# 96LED-Board-ALU.net
KiCad netlist of a schematic drawn in EAGLE
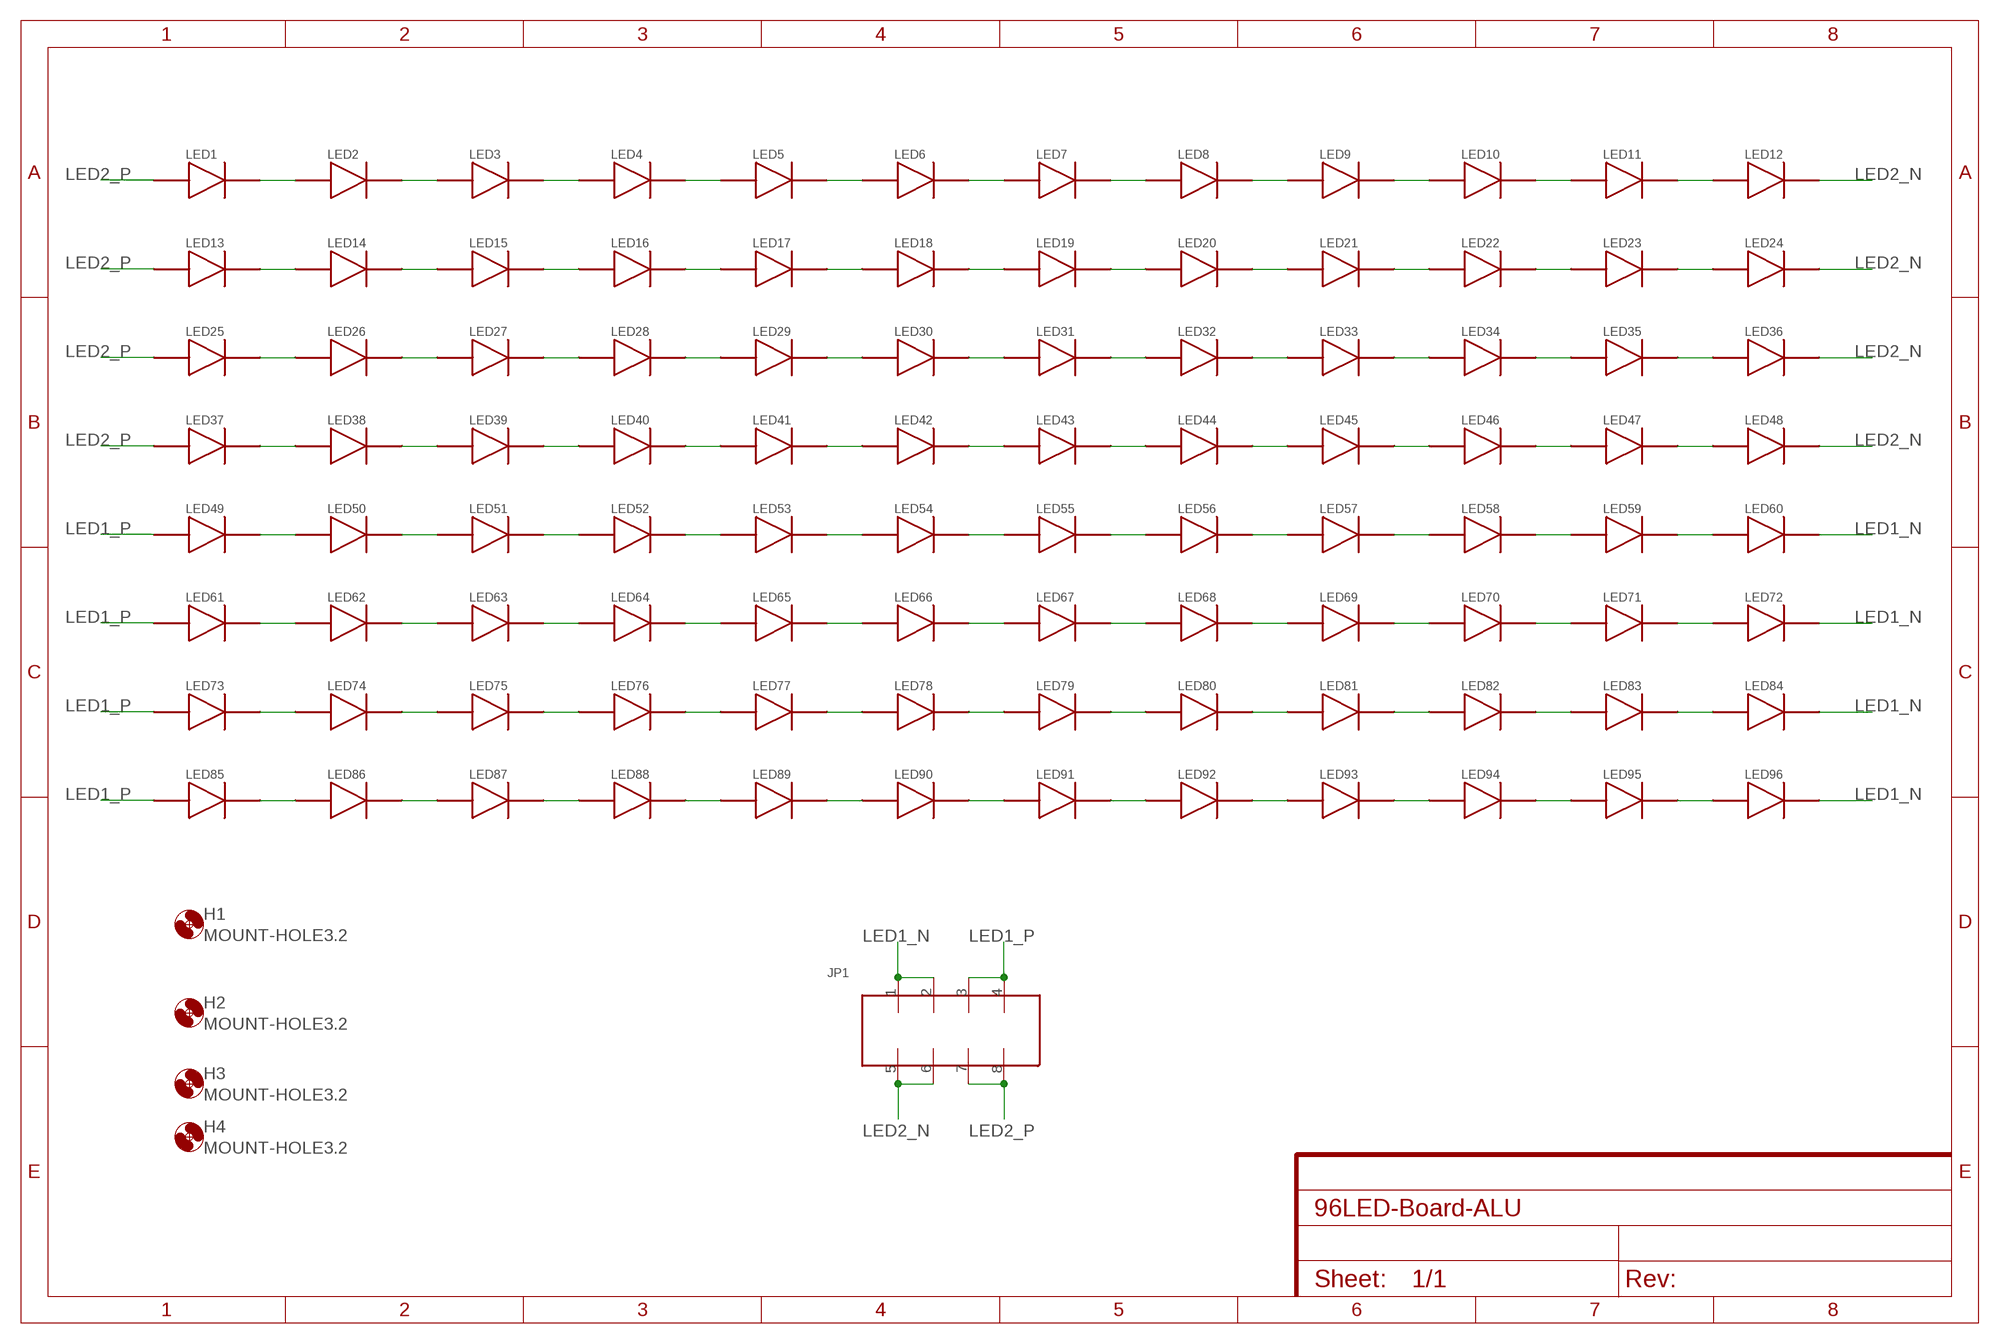
[diagram p0: schematic, sheet 1]

(export (version "E")
  (design (tool "Eeschema 10.0.6"))
  (components
    (comp (ref "H1")
      (value "MOUNT-HOLE3.2")
      (footprint "eagle-import:3,2")
      (libsource (lib "eagle-import") (part "MOUNT-HOLE3.2"))
    )
    (comp (ref "H2")
      (value "MOUNT-HOLE3.2")
      (footprint "eagle-import:3,2")
      (libsource (lib "eagle-import") (part "MOUNT-HOLE3.2"))
    )
    (comp (ref "H3")
      (value "MOUNT-HOLE3.2")
      (footprint "eagle-import:3,2")
      (libsource (lib "eagle-import") (part "MOUNT-HOLE3.2"))
    )
    (comp (ref "H4")
      (value "MOUNT-HOLE3.2")
      (footprint "eagle-import:3,2")
      (libsource (lib "eagle-import") (part "MOUNT-HOLE3.2"))
    )
    (comp (ref "JP1")
      (value "2X8P_2.54_FEMALE")
      (footprint "eagle-import:2X8_PIN_SMD_2.54-FEMALE")
      (libsource (lib "eagle-import") (part "2X8P_2.54_FEMALE"))
    )
    (comp (ref "LED1")
      (value "MP3030_N")
      (footprint "eagle-import:MP3030_N")
      (libsource (lib "eagle-import") (part "MP3030_N"))
    )
    (comp (ref "LED2")
      (value "MP3030_N")
      (footprint "eagle-import:MP3030_N")
      (libsource (lib "eagle-import") (part "MP3030_N"))
    )
    (comp (ref "LED3")
      (value "MP3030_N")
      (footprint "eagle-import:MP3030_N")
      (libsource (lib "eagle-import") (part "MP3030_N"))
    )
    (comp (ref "LED4")
      (value "MP3030_N")
      (footprint "eagle-import:MP3030_N")
      (libsource (lib "eagle-import") (part "MP3030_N"))
    )
    (comp (ref "LED5")
      (value "MP3030_N")
      (footprint "eagle-import:MP3030_N")
      (libsource (lib "eagle-import") (part "MP3030_N"))
    )
    (comp (ref "LED6")
      (value "MP3030_N")
      (footprint "eagle-import:MP3030_N")
      (libsource (lib "eagle-import") (part "MP3030_N"))
    )
    (comp (ref "LED7")
      (value "MP3030_N")
      (footprint "eagle-import:MP3030_N")
      (libsource (lib "eagle-import") (part "MP3030_N"))
    )
    (comp (ref "LED8")
      (value "MP3030_N")
      (footprint "eagle-import:MP3030_N")
      (libsource (lib "eagle-import") (part "MP3030_N"))
    )
    (comp (ref "LED9")
      (value "MP3030_N")
      (footprint "eagle-import:MP3030_N")
      (libsource (lib "eagle-import") (part "MP3030_N"))
    )
    (comp (ref "LED10")
      (value "MP3030_N")
      (footprint "eagle-import:MP3030_N")
      (libsource (lib "eagle-import") (part "MP3030_N"))
    )
    (comp (ref "LED11")
      (value "MP3030_N")
      (footprint "eagle-import:MP3030_N")
      (libsource (lib "eagle-import") (part "MP3030_N"))
    )
    (comp (ref "LED12")
      (value "MP3030_N")
      (footprint "eagle-import:MP3030_N")
      (libsource (lib "eagle-import") (part "MP3030_N"))
    )
    (comp (ref "LED13")
      (value "MP3030_N")
      (footprint "eagle-import:MP3030_N")
      (libsource (lib "eagle-import") (part "MP3030_N"))
    )
    (comp (ref "LED14")
      (value "MP3030_N")
      (footprint "eagle-import:MP3030_N")
      (libsource (lib "eagle-import") (part "MP3030_N"))
    )
    (comp (ref "LED15")
      (value "MP3030_N")
      (footprint "eagle-import:MP3030_N")
      (libsource (lib "eagle-import") (part "MP3030_N"))
    )
    (comp (ref "LED16")
      (value "MP3030_N")
      (footprint "eagle-import:MP3030_N")
      (libsource (lib "eagle-import") (part "MP3030_N"))
    )
    (comp (ref "LED17")
      (value "MP3030_N")
      (footprint "eagle-import:MP3030_N")
      (libsource (lib "eagle-import") (part "MP3030_N"))
    )
    (comp (ref "LED18")
      (value "MP3030_N")
      (footprint "eagle-import:MP3030_N")
      (libsource (lib "eagle-import") (part "MP3030_N"))
    )
    (comp (ref "LED19")
      (value "MP3030_N")
      (footprint "eagle-import:MP3030_N")
      (libsource (lib "eagle-import") (part "MP3030_N"))
    )
    (comp (ref "LED20")
      (value "MP3030_N")
      (footprint "eagle-import:MP3030_N")
      (libsource (lib "eagle-import") (part "MP3030_N"))
    )
    (comp (ref "LED21")
      (value "MP3030_N")
      (footprint "eagle-import:MP3030_N")
      (libsource (lib "eagle-import") (part "MP3030_N"))
    )
    (comp (ref "LED22")
      (value "MP3030_N")
      (footprint "eagle-import:MP3030_N")
      (libsource (lib "eagle-import") (part "MP3030_N"))
    )
    (comp (ref "LED23")
      (value "MP3030_N")
      (footprint "eagle-import:MP3030_N")
      (libsource (lib "eagle-import") (part "MP3030_N"))
    )
    (comp (ref "LED24")
      (value "MP3030_N")
      (footprint "eagle-import:MP3030_N")
      (libsource (lib "eagle-import") (part "MP3030_N"))
    )
    (comp (ref "LED25")
      (value "MP3030_N")
      (footprint "eagle-import:MP3030_N")
      (libsource (lib "eagle-import") (part "MP3030_N"))
    )
    (comp (ref "LED26")
      (value "MP3030_N")
      (footprint "eagle-import:MP3030_N")
      (libsource (lib "eagle-import") (part "MP3030_N"))
    )
    (comp (ref "LED27")
      (value "MP3030_N")
      (footprint "eagle-import:MP3030_N")
      (libsource (lib "eagle-import") (part "MP3030_N"))
    )
    (comp (ref "LED28")
      (value "MP3030_N")
      (footprint "eagle-import:MP3030_N")
      (libsource (lib "eagle-import") (part "MP3030_N"))
    )
    (comp (ref "LED29")
      (value "MP3030_N")
      (footprint "eagle-import:MP3030_N")
      (libsource (lib "eagle-import") (part "MP3030_N"))
    )
    (comp (ref "LED30")
      (value "MP3030_N")
      (footprint "eagle-import:MP3030_N")
      (libsource (lib "eagle-import") (part "MP3030_N"))
    )
    (comp (ref "LED31")
      (value "MP3030_N")
      (footprint "eagle-import:MP3030_N")
      (libsource (lib "eagle-import") (part "MP3030_N"))
    )
    (comp (ref "LED32")
      (value "MP3030_N")
      (footprint "eagle-import:MP3030_N")
      (libsource (lib "eagle-import") (part "MP3030_N"))
    )
    (comp (ref "LED33")
      (value "MP3030_N")
      (footprint "eagle-import:MP3030_N")
      (libsource (lib "eagle-import") (part "MP3030_N"))
    )
    (comp (ref "LED34")
      (value "MP3030_N")
      (footprint "eagle-import:MP3030_N")
      (libsource (lib "eagle-import") (part "MP3030_N"))
    )
    (comp (ref "LED35")
      (value "MP3030_N")
      (footprint "eagle-import:MP3030_N")
      (libsource (lib "eagle-import") (part "MP3030_N"))
    )
    (comp (ref "LED36")
      (value "MP3030_N")
      (footprint "eagle-import:MP3030_N")
      (libsource (lib "eagle-import") (part "MP3030_N"))
    )
    (comp (ref "LED37")
      (value "MP3030_N")
      (footprint "eagle-import:MP3030_N")
      (libsource (lib "eagle-import") (part "MP3030_N"))
    )
    (comp (ref "LED38")
      (value "MP3030_N")
      (footprint "eagle-import:MP3030_N")
      (libsource (lib "eagle-import") (part "MP3030_N"))
    )
    (comp (ref "LED39")
      (value "MP3030_N")
      (footprint "eagle-import:MP3030_N")
      (libsource (lib "eagle-import") (part "MP3030_N"))
    )
    (comp (ref "LED40")
      (value "MP3030_N")
      (footprint "eagle-import:MP3030_N")
      (libsource (lib "eagle-import") (part "MP3030_N"))
    )
    (comp (ref "LED41")
      (value "MP3030_N")
      (footprint "eagle-import:MP3030_N")
      (libsource (lib "eagle-import") (part "MP3030_N"))
    )
    (comp (ref "LED42")
      (value "MP3030_N")
      (footprint "eagle-import:MP3030_N")
      (libsource (lib "eagle-import") (part "MP3030_N"))
    )
    (comp (ref "LED43")
      (value "MP3030_N")
      (footprint "eagle-import:MP3030_N")
      (libsource (lib "eagle-import") (part "MP3030_N"))
    )
    (comp (ref "LED44")
      (value "MP3030_N")
      (footprint "eagle-import:MP3030_N")
      (libsource (lib "eagle-import") (part "MP3030_N"))
    )
    (comp (ref "LED45")
      (value "MP3030_N")
      (footprint "eagle-import:MP3030_N")
      (libsource (lib "eagle-import") (part "MP3030_N"))
    )
    (comp (ref "LED46")
      (value "MP3030_N")
      (footprint "eagle-import:MP3030_N")
      (libsource (lib "eagle-import") (part "MP3030_N"))
    )
    (comp (ref "LED47")
      (value "MP3030_N")
      (footprint "eagle-import:MP3030_N")
      (libsource (lib "eagle-import") (part "MP3030_N"))
    )
    (comp (ref "LED48")
      (value "MP3030_N")
      (footprint "eagle-import:MP3030_N")
      (libsource (lib "eagle-import") (part "MP3030_N"))
    )
    (comp (ref "LED49")
      (value "MP3030_N")
      (footprint "eagle-import:MP3030_N")
      (libsource (lib "eagle-import") (part "MP3030_N"))
    )
    (comp (ref "LED50")
      (value "MP3030_N")
      (footprint "eagle-import:MP3030_N")
      (libsource (lib "eagle-import") (part "MP3030_N"))
    )
    (comp (ref "LED51")
      (value "MP3030_N")
      (footprint "eagle-import:MP3030_N")
      (libsource (lib "eagle-import") (part "MP3030_N"))
    )
    (comp (ref "LED52")
      (value "MP3030_N")
      (footprint "eagle-import:MP3030_N")
      (libsource (lib "eagle-import") (part "MP3030_N"))
    )
    (comp (ref "LED53")
      (value "MP3030_N")
      (footprint "eagle-import:MP3030_N")
      (libsource (lib "eagle-import") (part "MP3030_N"))
    )
    (comp (ref "LED54")
      (value "MP3030_N")
      (footprint "eagle-import:MP3030_N")
      (libsource (lib "eagle-import") (part "MP3030_N"))
    )
    (comp (ref "LED55")
      (value "MP3030_N")
      (footprint "eagle-import:MP3030_N")
      (libsource (lib "eagle-import") (part "MP3030_N"))
    )
    (comp (ref "LED56")
      (value "MP3030_N")
      (footprint "eagle-import:MP3030_N")
      (libsource (lib "eagle-import") (part "MP3030_N"))
    )
    (comp (ref "LED57")
      (value "MP3030_N")
      (footprint "eagle-import:MP3030_N")
      (libsource (lib "eagle-import") (part "MP3030_N"))
    )
    (comp (ref "LED58")
      (value "MP3030_N")
      (footprint "eagle-import:MP3030_N")
      (libsource (lib "eagle-import") (part "MP3030_N"))
    )
    (comp (ref "LED59")
      (value "MP3030_N")
      (footprint "eagle-import:MP3030_N")
      (libsource (lib "eagle-import") (part "MP3030_N"))
    )
    (comp (ref "LED60")
      (value "MP3030_N")
      (footprint "eagle-import:MP3030_N")
      (libsource (lib "eagle-import") (part "MP3030_N"))
    )
    (comp (ref "LED61")
      (value "MP3030_N")
      (footprint "eagle-import:MP3030_N")
      (libsource (lib "eagle-import") (part "MP3030_N"))
    )
    (comp (ref "LED62")
      (value "MP3030_N")
      (footprint "eagle-import:MP3030_N")
      (libsource (lib "eagle-import") (part "MP3030_N"))
    )
    (comp (ref "LED63")
      (value "MP3030_N")
      (footprint "eagle-import:MP3030_N")
      (libsource (lib "eagle-import") (part "MP3030_N"))
    )
    (comp (ref "LED64")
      (value "MP3030_N")
      (footprint "eagle-import:MP3030_N")
      (libsource (lib "eagle-import") (part "MP3030_N"))
    )
    (comp (ref "LED65")
      (value "MP3030_N")
      (footprint "eagle-import:MP3030_N")
      (libsource (lib "eagle-import") (part "MP3030_N"))
    )
    (comp (ref "LED66")
      (value "MP3030_N")
      (footprint "eagle-import:MP3030_N")
      (libsource (lib "eagle-import") (part "MP3030_N"))
    )
    (comp (ref "LED67")
      (value "MP3030_N")
      (footprint "eagle-import:MP3030_N")
      (libsource (lib "eagle-import") (part "MP3030_N"))
    )
    (comp (ref "LED68")
      (value "MP3030_N")
      (footprint "eagle-import:MP3030_N")
      (libsource (lib "eagle-import") (part "MP3030_N"))
    )
    (comp (ref "LED69")
      (value "MP3030_N")
      (footprint "eagle-import:MP3030_N")
      (libsource (lib "eagle-import") (part "MP3030_N"))
    )
    (comp (ref "LED70")
      (value "MP3030_N")
      (footprint "eagle-import:MP3030_N")
      (libsource (lib "eagle-import") (part "MP3030_N"))
    )
    (comp (ref "LED71")
      (value "MP3030_N")
      (footprint "eagle-import:MP3030_N")
      (libsource (lib "eagle-import") (part "MP3030_N"))
    )
    (comp (ref "LED72")
      (value "MP3030_N")
      (footprint "eagle-import:MP3030_N")
      (libsource (lib "eagle-import") (part "MP3030_N"))
    )
    (comp (ref "LED73")
      (value "MP3030_N")
      (footprint "eagle-import:MP3030_N")
      (libsource (lib "eagle-import") (part "MP3030_N"))
    )
    (comp (ref "LED74")
      (value "MP3030_N")
      (footprint "eagle-import:MP3030_N")
      (libsource (lib "eagle-import") (part "MP3030_N"))
    )
    (comp (ref "LED75")
      (value "MP3030_N")
      (footprint "eagle-import:MP3030_N")
      (libsource (lib "eagle-import") (part "MP3030_N"))
    )
    (comp (ref "LED76")
      (value "MP3030_N")
      (footprint "eagle-import:MP3030_N")
      (libsource (lib "eagle-import") (part "MP3030_N"))
    )
    (comp (ref "LED77")
      (value "MP3030_N")
      (footprint "eagle-import:MP3030_N")
      (libsource (lib "eagle-import") (part "MP3030_N"))
    )
    (comp (ref "LED78")
      (value "MP3030_N")
      (footprint "eagle-import:MP3030_N")
      (libsource (lib "eagle-import") (part "MP3030_N"))
    )
    (comp (ref "LED79")
      (value "MP3030_N")
      (footprint "eagle-import:MP3030_N")
      (libsource (lib "eagle-import") (part "MP3030_N"))
    )
    (comp (ref "LED80")
      (value "MP3030_N")
      (footprint "eagle-import:MP3030_N")
      (libsource (lib "eagle-import") (part "MP3030_N"))
    )
    (comp (ref "LED81")
      (value "MP3030_N")
      (footprint "eagle-import:MP3030_N")
      (libsource (lib "eagle-import") (part "MP3030_N"))
    )
    (comp (ref "LED82")
      (value "MP3030_N")
      (footprint "eagle-import:MP3030_N")
      (libsource (lib "eagle-import") (part "MP3030_N"))
    )
    (comp (ref "LED83")
      (value "MP3030_N")
      (footprint "eagle-import:MP3030_N")
      (libsource (lib "eagle-import") (part "MP3030_N"))
    )
    (comp (ref "LED84")
      (value "MP3030_N")
      (footprint "eagle-import:MP3030_N")
      (libsource (lib "eagle-import") (part "MP3030_N"))
    )
    (comp (ref "LED85")
      (value "MP3030_N")
      (footprint "eagle-import:MP3030_N")
      (libsource (lib "eagle-import") (part "MP3030_N"))
    )
    (comp (ref "LED86")
      (value "MP3030_N")
      (footprint "eagle-import:MP3030_N")
      (libsource (lib "eagle-import") (part "MP3030_N"))
    )
    (comp (ref "LED87")
      (value "MP3030_N")
      (footprint "eagle-import:MP3030_N")
      (libsource (lib "eagle-import") (part "MP3030_N"))
    )
    (comp (ref "LED88")
      (value "MP3030_N")
      (footprint "eagle-import:MP3030_N")
      (libsource (lib "eagle-import") (part "MP3030_N"))
    )
    (comp (ref "LED89")
      (value "MP3030_N")
      (footprint "eagle-import:MP3030_N")
      (libsource (lib "eagle-import") (part "MP3030_N"))
    )
    (comp (ref "LED90")
      (value "MP3030_N")
      (footprint "eagle-import:MP3030_N")
      (libsource (lib "eagle-import") (part "MP3030_N"))
    )
    (comp (ref "LED91")
      (value "MP3030_N")
      (footprint "eagle-import:MP3030_N")
      (libsource (lib "eagle-import") (part "MP3030_N"))
    )
    (comp (ref "LED92")
      (value "MP3030_N")
      (footprint "eagle-import:MP3030_N")
      (libsource (lib "eagle-import") (part "MP3030_N"))
    )
    (comp (ref "LED93")
      (value "MP3030_N")
      (footprint "eagle-import:MP3030_N")
      (libsource (lib "eagle-import") (part "MP3030_N"))
    )
    (comp (ref "LED94")
      (value "MP3030_N")
      (footprint "eagle-import:MP3030_N")
      (libsource (lib "eagle-import") (part "MP3030_N"))
    )
    (comp (ref "LED95")
      (value "MP3030_N")
      (footprint "eagle-import:MP3030_N")
      (libsource (lib "eagle-import") (part "MP3030_N"))
    )
    (comp (ref "LED96")
      (value "MP3030_N")
      (footprint "eagle-import:MP3030_N")
      (libsource (lib "eagle-import") (part "MP3030_N"))
    )
  )
  (nets
    (net (code "1") (name "/LED1_N") (class "Default")
      (node (ref "JP1") (pin "1") (pinfunction "P$1_1") (pintype "bidirectional"))
      (node (ref "JP1") (pin "2") (pinfunction "P$2_2") (pintype "bidirectional"))
      (node (ref "LED60") (pin "2") (pinfunction "2_2") (pintype "bidirectional"))
      (node (ref "LED72") (pin "2") (pinfunction "2_2") (pintype "bidirectional"))
      (node (ref "LED84") (pin "2") (pinfunction "2_2") (pintype "bidirectional"))
      (node (ref "LED96") (pin "2") (pinfunction "2_2") (pintype "bidirectional"))
    )
    (net (code "2") (name "/LED1_P") (class "Default")
      (node (ref "JP1") (pin "3") (pinfunction "P$3_3") (pintype "bidirectional"))
      (node (ref "JP1") (pin "4") (pinfunction "P$4_4") (pintype "bidirectional"))
      (node (ref "LED49") (pin "1") (pinfunction "1_1") (pintype "bidirectional"))
      (node (ref "LED61") (pin "1") (pinfunction "1_1") (pintype "bidirectional"))
      (node (ref "LED73") (pin "1") (pinfunction "1_1") (pintype "bidirectional"))
      (node (ref "LED85") (pin "1") (pinfunction "1_1") (pintype "bidirectional"))
    )
    (net (code "3") (name "/LED2_N") (class "Default")
      (node (ref "JP1") (pin "5") (pinfunction "P$5_5") (pintype "bidirectional"))
      (node (ref "JP1") (pin "6") (pinfunction "P$6_6") (pintype "bidirectional"))
      (node (ref "LED12") (pin "2") (pinfunction "2_2") (pintype "bidirectional"))
      (node (ref "LED24") (pin "2") (pinfunction "2_2") (pintype "bidirectional"))
      (node (ref "LED36") (pin "2") (pinfunction "2_2") (pintype "bidirectional"))
      (node (ref "LED48") (pin "2") (pinfunction "2_2") (pintype "bidirectional"))
    )
    (net (code "4") (name "/LED2_P") (class "Default")
      (node (ref "JP1") (pin "7") (pinfunction "P$7_7") (pintype "bidirectional"))
      (node (ref "JP1") (pin "8") (pinfunction "P$8_8") (pintype "bidirectional"))
      (node (ref "LED1") (pin "1") (pinfunction "1_1") (pintype "bidirectional"))
      (node (ref "LED13") (pin "1") (pinfunction "1_1") (pintype "bidirectional"))
      (node (ref "LED25") (pin "1") (pinfunction "1_1") (pintype "bidirectional"))
      (node (ref "LED37") (pin "1") (pinfunction "1_1") (pintype "bidirectional"))
    )
    (net (code "5") (name "Net-(LED1-Pad2)") (class "Default")
      (node (ref "LED1") (pin "2") (pinfunction "2_2") (pintype "bidirectional"))
      (node (ref "LED2") (pin "1") (pinfunction "1_1") (pintype "bidirectional"))
    )
    (net (code "6") (name "Net-(LED2-Pad2)") (class "Default")
      (node (ref "LED2") (pin "2") (pinfunction "2_2") (pintype "bidirectional"))
      (node (ref "LED3") (pin "1") (pinfunction "1_1") (pintype "bidirectional"))
    )
    (net (code "7") (name "Net-(LED3-Pad2)") (class "Default")
      (node (ref "LED3") (pin "2") (pinfunction "2_2") (pintype "bidirectional"))
      (node (ref "LED4") (pin "1") (pinfunction "1_1") (pintype "bidirectional"))
    )
    (net (code "8") (name "Net-(LED4-Pad2)") (class "Default")
      (node (ref "LED4") (pin "2") (pinfunction "2_2") (pintype "bidirectional"))
      (node (ref "LED5") (pin "1") (pinfunction "1_1") (pintype "bidirectional"))
    )
    (net (code "9") (name "Net-(LED5-Pad2)") (class "Default")
      (node (ref "LED5") (pin "2") (pinfunction "2_2") (pintype "bidirectional"))
      (node (ref "LED6") (pin "1") (pinfunction "1_1") (pintype "bidirectional"))
    )
    (net (code "10") (name "Net-(LED6-Pad2)") (class "Default")
      (node (ref "LED6") (pin "2") (pinfunction "2_2") (pintype "bidirectional"))
      (node (ref "LED7") (pin "1") (pinfunction "1_1") (pintype "bidirectional"))
    )
    (net (code "11") (name "Net-(LED7-Pad2)") (class "Default")
      (node (ref "LED7") (pin "2") (pinfunction "2_2") (pintype "bidirectional"))
      (node (ref "LED8") (pin "1") (pinfunction "1_1") (pintype "bidirectional"))
    )
    (net (code "12") (name "Net-(LED8-Pad2)") (class "Default")
      (node (ref "LED8") (pin "2") (pinfunction "2_2") (pintype "bidirectional"))
      (node (ref "LED9") (pin "1") (pinfunction "1_1") (pintype "bidirectional"))
    )
    (net (code "13") (name "Net-(LED10-Pad1)") (class "Default")
      (node (ref "LED10") (pin "1") (pinfunction "1_1") (pintype "bidirectional"))
      (node (ref "LED9") (pin "2") (pinfunction "2_2") (pintype "bidirectional"))
    )
    (net (code "14") (name "Net-(LED10-Pad2)") (class "Default")
      (node (ref "LED10") (pin "2") (pinfunction "2_2") (pintype "bidirectional"))
      (node (ref "LED11") (pin "1") (pinfunction "1_1") (pintype "bidirectional"))
    )
    (net (code "15") (name "Net-(LED11-Pad2)") (class "Default")
      (node (ref "LED11") (pin "2") (pinfunction "2_2") (pintype "bidirectional"))
      (node (ref "LED12") (pin "1") (pinfunction "1_1") (pintype "bidirectional"))
    )
    (net (code "16") (name "Net-(LED13-Pad2)") (class "Default")
      (node (ref "LED13") (pin "2") (pinfunction "2_2") (pintype "bidirectional"))
      (node (ref "LED14") (pin "1") (pinfunction "1_1") (pintype "bidirectional"))
    )
    (net (code "17") (name "Net-(LED14-Pad2)") (class "Default")
      (node (ref "LED14") (pin "2") (pinfunction "2_2") (pintype "bidirectional"))
      (node (ref "LED15") (pin "1") (pinfunction "1_1") (pintype "bidirectional"))
    )
    (net (code "18") (name "Net-(LED15-Pad2)") (class "Default")
      (node (ref "LED15") (pin "2") (pinfunction "2_2") (pintype "bidirectional"))
      (node (ref "LED16") (pin "1") (pinfunction "1_1") (pintype "bidirectional"))
    )
    (net (code "19") (name "Net-(LED16-Pad2)") (class "Default")
      (node (ref "LED16") (pin "2") (pinfunction "2_2") (pintype "bidirectional"))
      (node (ref "LED17") (pin "1") (pinfunction "1_1") (pintype "bidirectional"))
    )
    (net (code "20") (name "Net-(LED17-Pad2)") (class "Default")
      (node (ref "LED17") (pin "2") (pinfunction "2_2") (pintype "bidirectional"))
      (node (ref "LED18") (pin "1") (pinfunction "1_1") (pintype "bidirectional"))
    )
    (net (code "21") (name "Net-(LED18-Pad2)") (class "Default")
      (node (ref "LED18") (pin "2") (pinfunction "2_2") (pintype "bidirectional"))
      (node (ref "LED19") (pin "1") (pinfunction "1_1") (pintype "bidirectional"))
    )
    (net (code "22") (name "Net-(LED19-Pad2)") (class "Default")
      (node (ref "LED19") (pin "2") (pinfunction "2_2") (pintype "bidirectional"))
      (node (ref "LED20") (pin "1") (pinfunction "1_1") (pintype "bidirectional"))
    )
    (net (code "23") (name "Net-(LED20-Pad2)") (class "Default")
      (node (ref "LED20") (pin "2") (pinfunction "2_2") (pintype "bidirectional"))
      (node (ref "LED21") (pin "1") (pinfunction "1_1") (pintype "bidirectional"))
    )
    (net (code "24") (name "Net-(LED21-Pad2)") (class "Default")
      (node (ref "LED21") (pin "2") (pinfunction "2_2") (pintype "bidirectional"))
      (node (ref "LED22") (pin "1") (pinfunction "1_1") (pintype "bidirectional"))
    )
    (net (code "25") (name "Net-(LED22-Pad2)") (class "Default")
      (node (ref "LED22") (pin "2") (pinfunction "2_2") (pintype "bidirectional"))
      (node (ref "LED23") (pin "1") (pinfunction "1_1") (pintype "bidirectional"))
    )
    (net (code "26") (name "Net-(LED23-Pad2)") (class "Default")
      (node (ref "LED23") (pin "2") (pinfunction "2_2") (pintype "bidirectional"))
      (node (ref "LED24") (pin "1") (pinfunction "1_1") (pintype "bidirectional"))
    )
    (net (code "27") (name "Net-(LED25-Pad2)") (class "Default")
      (node (ref "LED25") (pin "2") (pinfunction "2_2") (pintype "bidirectional"))
      (node (ref "LED26") (pin "1") (pinfunction "1_1") (pintype "bidirectional"))
    )
    (net (code "28") (name "Net-(LED26-Pad2)") (class "Default")
      (node (ref "LED26") (pin "2") (pinfunction "2_2") (pintype "bidirectional"))
      (node (ref "LED27") (pin "1") (pinfunction "1_1") (pintype "bidirectional"))
    )
    (net (code "29") (name "Net-(LED27-Pad2)") (class "Default")
      (node (ref "LED27") (pin "2") (pinfunction "2_2") (pintype "bidirectional"))
      (node (ref "LED28") (pin "1") (pinfunction "1_1") (pintype "bidirectional"))
    )
    (net (code "30") (name "Net-(LED28-Pad2)") (class "Default")
      (node (ref "LED28") (pin "2") (pinfunction "2_2") (pintype "bidirectional"))
      (node (ref "LED29") (pin "1") (pinfunction "1_1") (pintype "bidirectional"))
    )
    (net (code "31") (name "Net-(LED29-Pad2)") (class "Default")
      (node (ref "LED29") (pin "2") (pinfunction "2_2") (pintype "bidirectional"))
      (node (ref "LED30") (pin "1") (pinfunction "1_1") (pintype "bidirectional"))
    )
    (net (code "32") (name "Net-(LED30-Pad2)") (class "Default")
      (node (ref "LED30") (pin "2") (pinfunction "2_2") (pintype "bidirectional"))
      (node (ref "LED31") (pin "1") (pinfunction "1_1") (pintype "bidirectional"))
    )
    (net (code "33") (name "Net-(LED31-Pad2)") (class "Default")
      (node (ref "LED31") (pin "2") (pinfunction "2_2") (pintype "bidirectional"))
      (node (ref "LED32") (pin "1") (pinfunction "1_1") (pintype "bidirectional"))
    )
    (net (code "34") (name "Net-(LED32-Pad2)") (class "Default")
      (node (ref "LED32") (pin "2") (pinfunction "2_2") (pintype "bidirectional"))
      (node (ref "LED33") (pin "1") (pinfunction "1_1") (pintype "bidirectional"))
    )
    (net (code "35") (name "Net-(LED33-Pad2)") (class "Default")
      (node (ref "LED33") (pin "2") (pinfunction "2_2") (pintype "bidirectional"))
      (node (ref "LED34") (pin "1") (pinfunction "1_1") (pintype "bidirectional"))
    )
    (net (code "36") (name "Net-(LED34-Pad2)") (class "Default")
      (node (ref "LED34") (pin "2") (pinfunction "2_2") (pintype "bidirectional"))
      (node (ref "LED35") (pin "1") (pinfunction "1_1") (pintype "bidirectional"))
    )
    (net (code "37") (name "Net-(LED35-Pad2)") (class "Default")
      (node (ref "LED35") (pin "2") (pinfunction "2_2") (pintype "bidirectional"))
      (node (ref "LED36") (pin "1") (pinfunction "1_1") (pintype "bidirectional"))
    )
    (net (code "38") (name "Net-(LED37-Pad2)") (class "Default")
      (node (ref "LED37") (pin "2") (pinfunction "2_2") (pintype "bidirectional"))
      (node (ref "LED38") (pin "1") (pinfunction "1_1") (pintype "bidirectional"))
    )
    (net (code "39") (name "Net-(LED38-Pad2)") (class "Default")
      (node (ref "LED38") (pin "2") (pinfunction "2_2") (pintype "bidirectional"))
      (node (ref "LED39") (pin "1") (pinfunction "1_1") (pintype "bidirectional"))
    )
    (net (code "40") (name "Net-(LED39-Pad2)") (class "Default")
      (node (ref "LED39") (pin "2") (pinfunction "2_2") (pintype "bidirectional"))
      (node (ref "LED40") (pin "1") (pinfunction "1_1") (pintype "bidirectional"))
    )
    (net (code "41") (name "Net-(LED40-Pad2)") (class "Default")
      (node (ref "LED40") (pin "2") (pinfunction "2_2") (pintype "bidirectional"))
      (node (ref "LED41") (pin "1") (pinfunction "1_1") (pintype "bidirectional"))
    )
    (net (code "42") (name "Net-(LED41-Pad2)") (class "Default")
      (node (ref "LED41") (pin "2") (pinfunction "2_2") (pintype "bidirectional"))
      (node (ref "LED42") (pin "1") (pinfunction "1_1") (pintype "bidirectional"))
    )
    (net (code "43") (name "Net-(LED42-Pad2)") (class "Default")
      (node (ref "LED42") (pin "2") (pinfunction "2_2") (pintype "bidirectional"))
      (node (ref "LED43") (pin "1") (pinfunction "1_1") (pintype "bidirectional"))
    )
    (net (code "44") (name "Net-(LED43-Pad2)") (class "Default")
      (node (ref "LED43") (pin "2") (pinfunction "2_2") (pintype "bidirectional"))
      (node (ref "LED44") (pin "1") (pinfunction "1_1") (pintype "bidirectional"))
    )
    (net (code "45") (name "Net-(LED44-Pad2)") (class "Default")
      (node (ref "LED44") (pin "2") (pinfunction "2_2") (pintype "bidirectional"))
      (node (ref "LED45") (pin "1") (pinfunction "1_1") (pintype "bidirectional"))
    )
    (net (code "46") (name "Net-(LED45-Pad2)") (class "Default")
      (node (ref "LED45") (pin "2") (pinfunction "2_2") (pintype "bidirectional"))
      (node (ref "LED46") (pin "1") (pinfunction "1_1") (pintype "bidirectional"))
    )
    (net (code "47") (name "Net-(LED46-Pad2)") (class "Default")
      (node (ref "LED46") (pin "2") (pinfunction "2_2") (pintype "bidirectional"))
      (node (ref "LED47") (pin "1") (pinfunction "1_1") (pintype "bidirectional"))
    )
    (net (code "48") (name "Net-(LED47-Pad2)") (class "Default")
      (node (ref "LED47") (pin "2") (pinfunction "2_2") (pintype "bidirectional"))
      (node (ref "LED48") (pin "1") (pinfunction "1_1") (pintype "bidirectional"))
    )
    (net (code "49") (name "Net-(LED49-Pad2)") (class "Default")
      (node (ref "LED49") (pin "2") (pinfunction "2_2") (pintype "bidirectional"))
      (node (ref "LED50") (pin "1") (pinfunction "1_1") (pintype "bidirectional"))
    )
    (net (code "50") (name "Net-(LED50-Pad2)") (class "Default")
      (node (ref "LED50") (pin "2") (pinfunction "2_2") (pintype "bidirectional"))
      (node (ref "LED51") (pin "1") (pinfunction "1_1") (pintype "bidirectional"))
    )
    (net (code "51") (name "Net-(LED51-Pad2)") (class "Default")
      (node (ref "LED51") (pin "2") (pinfunction "2_2") (pintype "bidirectional"))
      (node (ref "LED52") (pin "1") (pinfunction "1_1") (pintype "bidirectional"))
    )
    (net (code "52") (name "Net-(LED52-Pad2)") (class "Default")
      (node (ref "LED52") (pin "2") (pinfunction "2_2") (pintype "bidirectional"))
      (node (ref "LED53") (pin "1") (pinfunction "1_1") (pintype "bidirectional"))
    )
    (net (code "53") (name "Net-(LED53-Pad2)") (class "Default")
      (node (ref "LED53") (pin "2") (pinfunction "2_2") (pintype "bidirectional"))
      (node (ref "LED54") (pin "1") (pinfunction "1_1") (pintype "bidirectional"))
    )
    (net (code "54") (name "Net-(LED54-Pad2)") (class "Default")
      (node (ref "LED54") (pin "2") (pinfunction "2_2") (pintype "bidirectional"))
      (node (ref "LED55") (pin "1") (pinfunction "1_1") (pintype "bidirectional"))
    )
    (net (code "55") (name "Net-(LED55-Pad2)") (class "Default")
      (node (ref "LED55") (pin "2") (pinfunction "2_2") (pintype "bidirectional"))
      (node (ref "LED56") (pin "1") (pinfunction "1_1") (pintype "bidirectional"))
    )
    (net (code "56") (name "Net-(LED56-Pad2)") (class "Default")
      (node (ref "LED56") (pin "2") (pinfunction "2_2") (pintype "bidirectional"))
      (node (ref "LED57") (pin "1") (pinfunction "1_1") (pintype "bidirectional"))
    )
    (net (code "57") (name "Net-(LED57-Pad2)") (class "Default")
      (node (ref "LED57") (pin "2") (pinfunction "2_2") (pintype "bidirectional"))
      (node (ref "LED58") (pin "1") (pinfunction "1_1") (pintype "bidirectional"))
    )
    (net (code "58") (name "Net-(LED58-Pad2)") (class "Default")
      (node (ref "LED58") (pin "2") (pinfunction "2_2") (pintype "bidirectional"))
      (node (ref "LED59") (pin "1") (pinfunction "1_1") (pintype "bidirectional"))
    )
    (net (code "59") (name "Net-(LED59-Pad2)") (class "Default")
      (node (ref "LED59") (pin "2") (pinfunction "2_2") (pintype "bidirectional"))
      (node (ref "LED60") (pin "1") (pinfunction "1_1") (pintype "bidirectional"))
    )
    (net (code "60") (name "Net-(LED61-Pad2)") (class "Default")
      (node (ref "LED61") (pin "2") (pinfunction "2_2") (pintype "bidirectional"))
      (node (ref "LED62") (pin "1") (pinfunction "1_1") (pintype "bidirectional"))
    )
    (net (code "61") (name "Net-(LED62-Pad2)") (class "Default")
      (node (ref "LED62") (pin "2") (pinfunction "2_2") (pintype "bidirectional"))
      (node (ref "LED63") (pin "1") (pinfunction "1_1") (pintype "bidirectional"))
    )
    (net (code "62") (name "Net-(LED63-Pad2)") (class "Default")
      (node (ref "LED63") (pin "2") (pinfunction "2_2") (pintype "bidirectional"))
      (node (ref "LED64") (pin "1") (pinfunction "1_1") (pintype "bidirectional"))
    )
    (net (code "63") (name "Net-(LED64-Pad2)") (class "Default")
      (node (ref "LED64") (pin "2") (pinfunction "2_2") (pintype "bidirectional"))
      (node (ref "LED65") (pin "1") (pinfunction "1_1") (pintype "bidirectional"))
    )
    (net (code "64") (name "Net-(LED65-Pad2)") (class "Default")
      (node (ref "LED65") (pin "2") (pinfunction "2_2") (pintype "bidirectional"))
      (node (ref "LED66") (pin "1") (pinfunction "1_1") (pintype "bidirectional"))
    )
    (net (code "65") (name "Net-(LED66-Pad2)") (class "Default")
      (node (ref "LED66") (pin "2") (pinfunction "2_2") (pintype "bidirectional"))
      (node (ref "LED67") (pin "1") (pinfunction "1_1") (pintype "bidirectional"))
    )
    (net (code "66") (name "Net-(LED67-Pad2)") (class "Default")
      (node (ref "LED67") (pin "2") (pinfunction "2_2") (pintype "bidirectional"))
      (node (ref "LED68") (pin "1") (pinfunction "1_1") (pintype "bidirectional"))
    )
    (net (code "67") (name "Net-(LED68-Pad2)") (class "Default")
      (node (ref "LED68") (pin "2") (pinfunction "2_2") (pintype "bidirectional"))
      (node (ref "LED69") (pin "1") (pinfunction "1_1") (pintype "bidirectional"))
    )
    (net (code "68") (name "Net-(LED69-Pad2)") (class "Default")
      (node (ref "LED69") (pin "2") (pinfunction "2_2") (pintype "bidirectional"))
      (node (ref "LED70") (pin "1") (pinfunction "1_1") (pintype "bidirectional"))
    )
    (net (code "69") (name "Net-(LED70-Pad2)") (class "Default")
      (node (ref "LED70") (pin "2") (pinfunction "2_2") (pintype "bidirectional"))
      (node (ref "LED71") (pin "1") (pinfunction "1_1") (pintype "bidirectional"))
    )
    (net (code "70") (name "Net-(LED71-Pad2)") (class "Default")
      (node (ref "LED71") (pin "2") (pinfunction "2_2") (pintype "bidirectional"))
      (node (ref "LED72") (pin "1") (pinfunction "1_1") (pintype "bidirectional"))
    )
    (net (code "71") (name "Net-(LED73-Pad2)") (class "Default")
      (node (ref "LED73") (pin "2") (pinfunction "2_2") (pintype "bidirectional"))
      (node (ref "LED74") (pin "1") (pinfunction "1_1") (pintype "bidirectional"))
    )
    (net (code "72") (name "Net-(LED74-Pad2)") (class "Default")
      (node (ref "LED74") (pin "2") (pinfunction "2_2") (pintype "bidirectional"))
      (node (ref "LED75") (pin "1") (pinfunction "1_1") (pintype "bidirectional"))
    )
    (net (code "73") (name "Net-(LED75-Pad2)") (class "Default")
      (node (ref "LED75") (pin "2") (pinfunction "2_2") (pintype "bidirectional"))
      (node (ref "LED76") (pin "1") (pinfunction "1_1") (pintype "bidirectional"))
    )
    (net (code "74") (name "Net-(LED76-Pad2)") (class "Default")
      (node (ref "LED76") (pin "2") (pinfunction "2_2") (pintype "bidirectional"))
      (node (ref "LED77") (pin "1") (pinfunction "1_1") (pintype "bidirectional"))
    )
    (net (code "75") (name "Net-(LED77-Pad2)") (class "Default")
      (node (ref "LED77") (pin "2") (pinfunction "2_2") (pintype "bidirectional"))
      (node (ref "LED78") (pin "1") (pinfunction "1_1") (pintype "bidirectional"))
    )
    (net (code "76") (name "Net-(LED78-Pad2)") (class "Default")
      (node (ref "LED78") (pin "2") (pinfunction "2_2") (pintype "bidirectional"))
      (node (ref "LED79") (pin "1") (pinfunction "1_1") (pintype "bidirectional"))
    )
    (net (code "77") (name "Net-(LED79-Pad2)") (class "Default")
      (node (ref "LED79") (pin "2") (pinfunction "2_2") (pintype "bidirectional"))
      (node (ref "LED80") (pin "1") (pinfunction "1_1") (pintype "bidirectional"))
    )
    (net (code "78") (name "Net-(LED80-Pad2)") (class "Default")
      (node (ref "LED80") (pin "2") (pinfunction "2_2") (pintype "bidirectional"))
      (node (ref "LED81") (pin "1") (pinfunction "1_1") (pintype "bidirectional"))
    )
    (net (code "79") (name "Net-(LED81-Pad2)") (class "Default")
      (node (ref "LED81") (pin "2") (pinfunction "2_2") (pintype "bidirectional"))
      (node (ref "LED82") (pin "1") (pinfunction "1_1") (pintype "bidirectional"))
    )
    (net (code "80") (name "Net-(LED82-Pad2)") (class "Default")
      (node (ref "LED82") (pin "2") (pinfunction "2_2") (pintype "bidirectional"))
      (node (ref "LED83") (pin "1") (pinfunction "1_1") (pintype "bidirectional"))
    )
    (net (code "81") (name "Net-(LED83-Pad2)") (class "Default")
      (node (ref "LED83") (pin "2") (pinfunction "2_2") (pintype "bidirectional"))
      (node (ref "LED84") (pin "1") (pinfunction "1_1") (pintype "bidirectional"))
    )
    (net (code "82") (name "Net-(LED85-Pad2)") (class "Default")
      (node (ref "LED85") (pin "2") (pinfunction "2_2") (pintype "bidirectional"))
      (node (ref "LED86") (pin "1") (pinfunction "1_1") (pintype "bidirectional"))
    )
    (net (code "83") (name "Net-(LED86-Pad2)") (class "Default")
      (node (ref "LED86") (pin "2") (pinfunction "2_2") (pintype "bidirectional"))
      (node (ref "LED87") (pin "1") (pinfunction "1_1") (pintype "bidirectional"))
    )
    (net (code "84") (name "Net-(LED87-Pad2)") (class "Default")
      (node (ref "LED87") (pin "2") (pinfunction "2_2") (pintype "bidirectional"))
      (node (ref "LED88") (pin "1") (pinfunction "1_1") (pintype "bidirectional"))
    )
    (net (code "85") (name "Net-(LED88-Pad2)") (class "Default")
      (node (ref "LED88") (pin "2") (pinfunction "2_2") (pintype "bidirectional"))
      (node (ref "LED89") (pin "1") (pinfunction "1_1") (pintype "bidirectional"))
    )
    (net (code "86") (name "Net-(LED89-Pad2)") (class "Default")
      (node (ref "LED89") (pin "2") (pinfunction "2_2") (pintype "bidirectional"))
      (node (ref "LED90") (pin "1") (pinfunction "1_1") (pintype "bidirectional"))
    )
    (net (code "87") (name "Net-(LED90-Pad2)") (class "Default")
      (node (ref "LED90") (pin "2") (pinfunction "2_2") (pintype "bidirectional"))
      (node (ref "LED91") (pin "1") (pinfunction "1_1") (pintype "bidirectional"))
    )
    (net (code "88") (name "Net-(LED91-Pad2)") (class "Default")
      (node (ref "LED91") (pin "2") (pinfunction "2_2") (pintype "bidirectional"))
      (node (ref "LED92") (pin "1") (pinfunction "1_1") (pintype "bidirectional"))
    )
    (net (code "89") (name "Net-(LED92-Pad2)") (class "Default")
      (node (ref "LED92") (pin "2") (pinfunction "2_2") (pintype "bidirectional"))
      (node (ref "LED93") (pin "1") (pinfunction "1_1") (pintype "bidirectional"))
    )
    (net (code "90") (name "Net-(LED93-Pad2)") (class "Default")
      (node (ref "LED93") (pin "2") (pinfunction "2_2") (pintype "bidirectional"))
      (node (ref "LED94") (pin "1") (pinfunction "1_1") (pintype "bidirectional"))
    )
    (net (code "91") (name "Net-(LED94-Pad2)") (class "Default")
      (node (ref "LED94") (pin "2") (pinfunction "2_2") (pintype "bidirectional"))
      (node (ref "LED95") (pin "1") (pinfunction "1_1") (pintype "bidirectional"))
    )
    (net (code "92") (name "Net-(LED95-Pad2)") (class "Default")
      (node (ref "LED95") (pin "2") (pinfunction "2_2") (pintype "bidirectional"))
      (node (ref "LED96") (pin "1") (pinfunction "1_1") (pintype "bidirectional"))
    )
  )
)
